# BT8670.net
KiCad netlist of a schematic drawn in Altium Designer
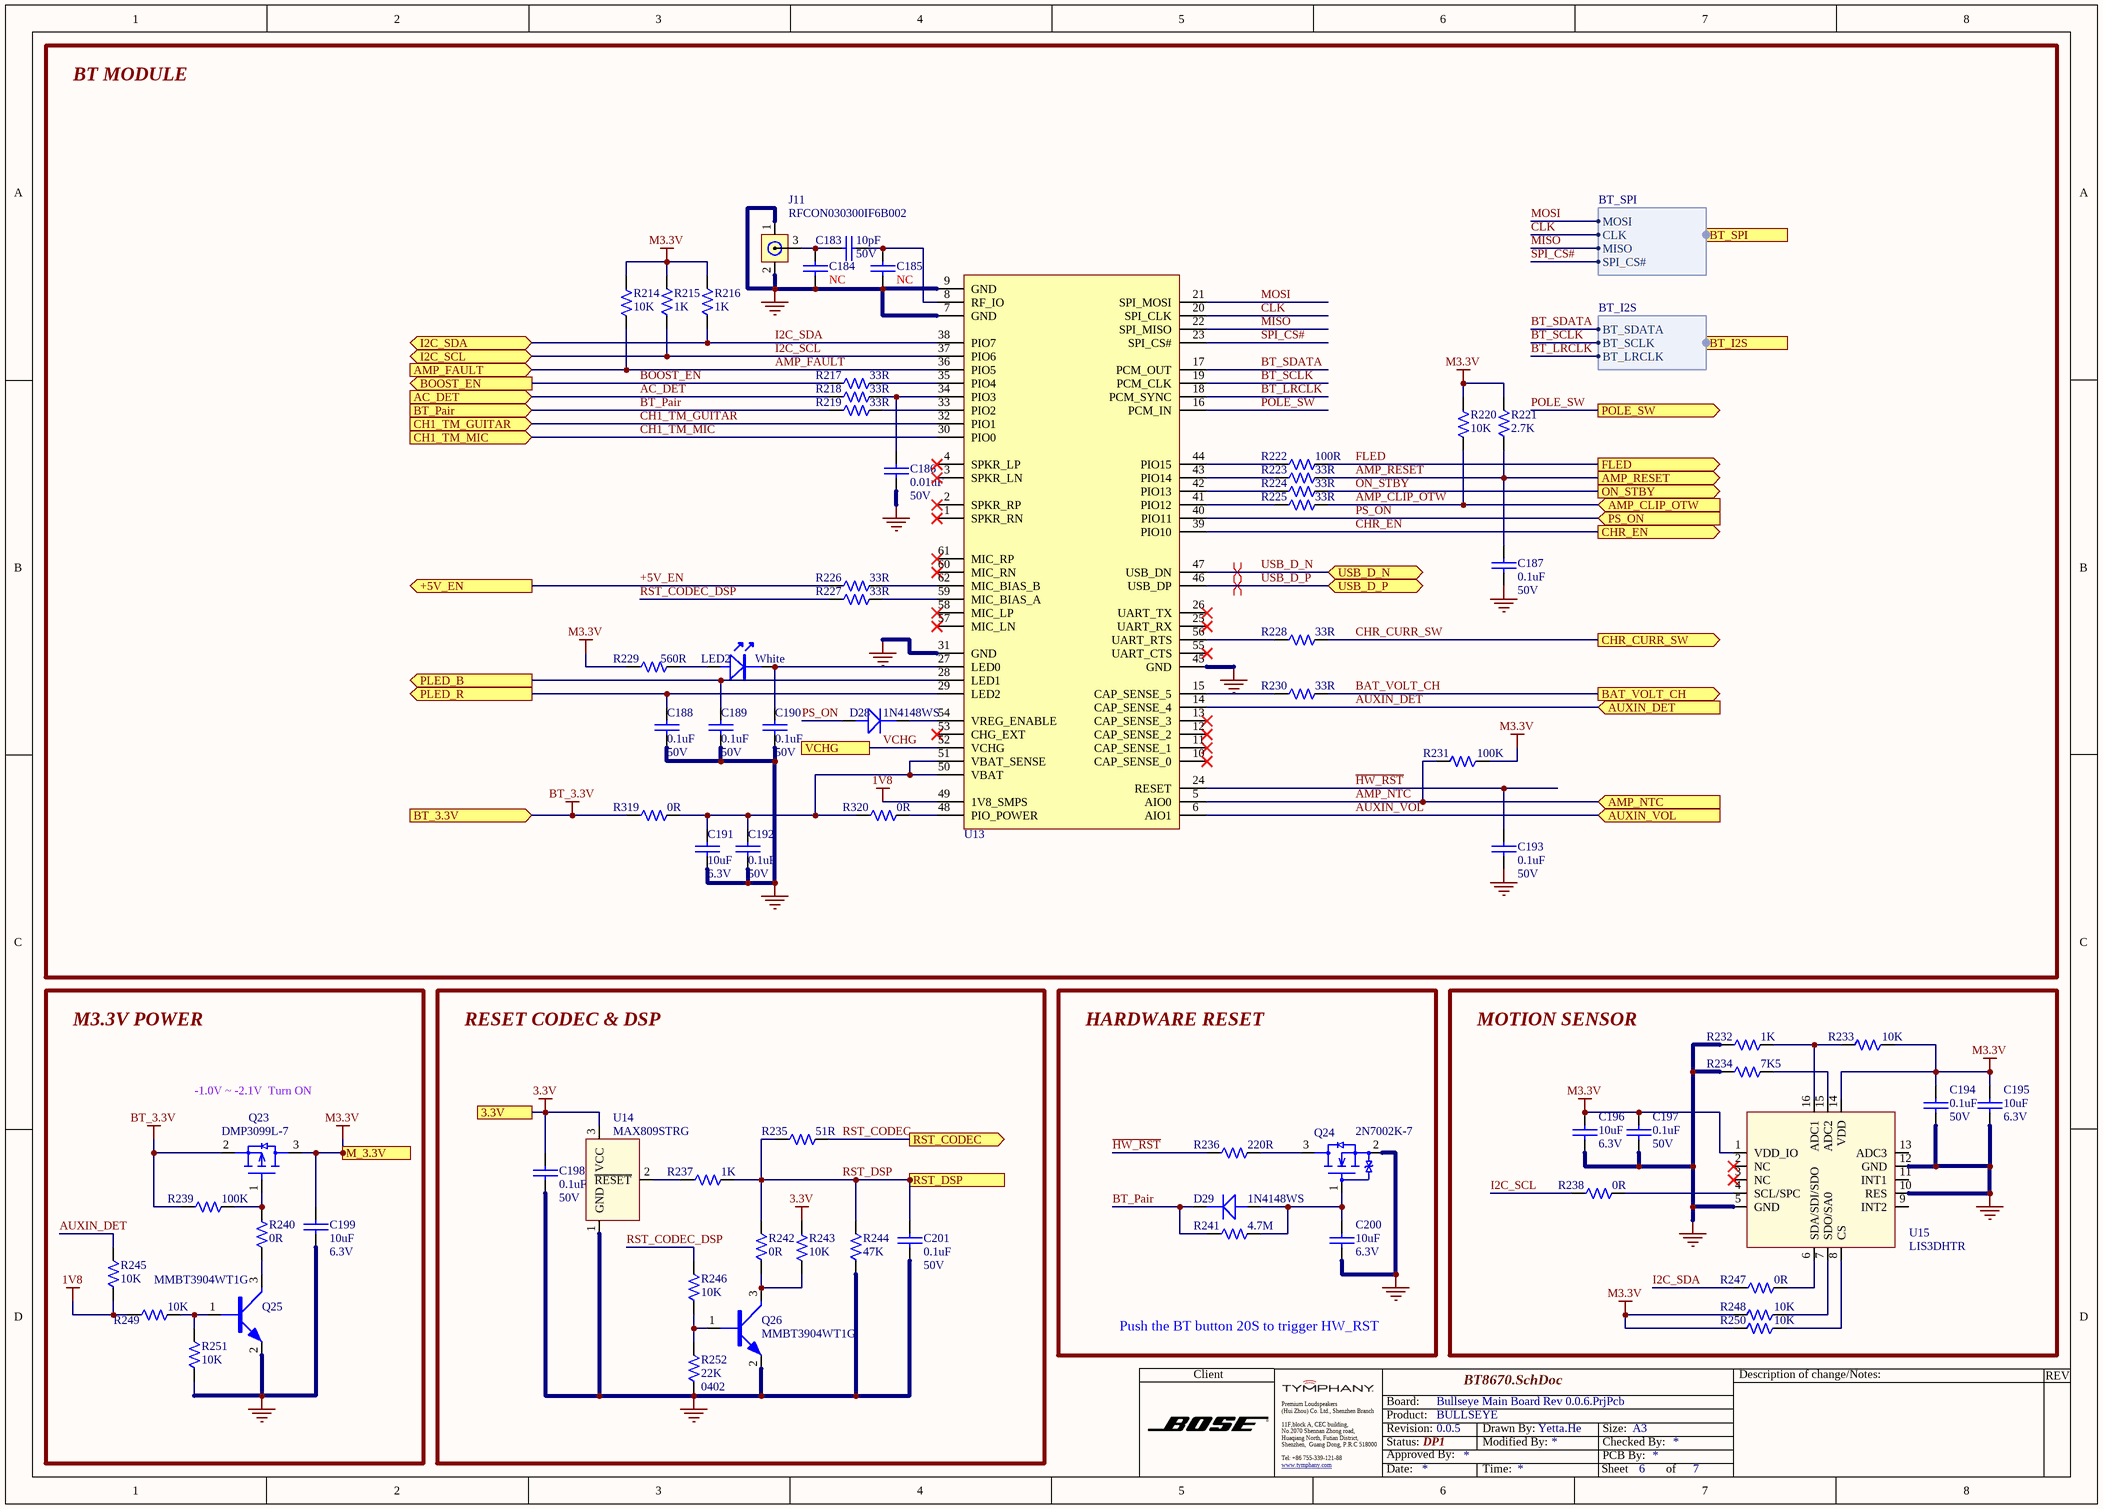
[diagram p0: BT8670.SchDoc]

(export (version "E")
  (design (tool "Eeschema 10.0.6"))
  (components
    (comp (ref "C183")
      (value "10pF")
      (footprint "CAPC0402-RW")
      (description "CHIP CAP 5% 50V 0402 NPO 10pF")
      (fields
        (field (name "TOLERANCE") "5%")
        (field (name "VOLTAGE") "50V")
        (field (name "Comment") "PWL410371-1000")
        (field (name "CREATE_NAME") "TOM@Deftronics")
      )
      (libsource (lib "P-Capacitors") (part "CAP0402 10pF 50V 5%"))
    )
    (comp (ref "C184")
      (value "NC")
      (footprint "CAPC0402-RW")
      (fields (field (name "Comment") "CAP0402 NC") (field (name "CREATE_NAME") "Tom"))
      (libsource (lib "Temporary") (part "CAP0402 NC"))
    )
    (comp (ref "C185")
      (value "NC")
      (footprint "CAPC0402-RW")
      (fields (field (name "Comment") "CAP0402 NC") (field (name "CREATE_NAME") "Tom"))
      (libsource (lib "Temporary") (part "CAP0402 NC"))
    )
    (comp (ref "C186")
      (value "0.01uF")
      (footprint "CAPC0402-RW")
      (description "CAP, CER, 0.01uF, 10%, 50V, X7R, 0402, RoHS")
      (fields
        (field (name "TOLERANCE") "10%")
        (field (name "VOLTAGE") "50V")
        (field (name "Comment") "PWL456470-1030")
        (field (name "CREATE_NAME") "Evan@Deftronics")
      )
      (libsource (lib "P-Capacitors") (part "CAP0402 0.01uF 50V 10%"))
    )
    (comp (ref "C187")
      (value "0.1uF")
      (footprint "CAPC0402-RW")
      (description "CAP X7R .10UF 50V +-10% 0402 WALSIN L")
      (fields
        (field (name "TOLERANCE") "10%")
        (field (name "VOLTAGE") "50V")
        (field (name "Comment") "PWL456470-1040")
        (field (name "CREATE_NAME") "TOM@Deftronics")
      )
      (libsource (lib "P-Capacitors") (part "CAP0402 0.1uF 50V 10%"))
    )
    (comp (ref "C188")
      (value "0.1uF")
      (footprint "CAPC0402-RW")
      (description "CAP X7R .10UF 50V +-10% 0402 WALSIN L")
      (fields
        (field (name "TOLERANCE") "10%")
        (field (name "VOLTAGE") "50V")
        (field (name "Comment") "PWL456470-1040")
        (field (name "CREATE_NAME") "TOM@Deftronics")
      )
      (libsource (lib "P-Capacitors") (part "CAP0402 0.1uF 50V 10%"))
    )
    (comp (ref "C189")
      (value "0.1uF")
      (footprint "CAPC0402-RW")
      (description "CAP X7R .10UF 50V +-10% 0402 WALSIN L")
      (fields
        (field (name "TOLERANCE") "10%")
        (field (name "VOLTAGE") "50V")
        (field (name "Comment") "PWL456470-1040")
        (field (name "CREATE_NAME") "TOM@Deftronics")
      )
      (libsource (lib "P-Capacitors") (part "CAP0402 0.1uF 50V 10%"))
    )
    (comp (ref "C190")
      (value "0.1uF")
      (footprint "CAPC0402-RW")
      (description "CAP X7R .10UF 50V +-10% 0402 WALSIN L")
      (fields
        (field (name "TOLERANCE") "10%")
        (field (name "VOLTAGE") "50V")
        (field (name "Comment") "PWL456470-1040")
        (field (name "CREATE_NAME") "TOM@Deftronics")
      )
      (libsource (lib "P-Capacitors") (part "CAP0402 0.1uF 50V 10%"))
    )
    (comp (ref "C191")
      (value "10uF")
      (footprint "CAPC0603-RW")
      (description "CAP X5R 10UF 6.3V +-10% 0603 SAMSUN L")
      (fields
        (field (name "MFG") "SAMSUNG")
        (field (name "MFG PART") "CL10A106KQ8NNNC")
        (field (name "VOLTAGE") "6.3V")
        (field (name "CREATE_NAME") "Nathan")
      )
      (libsource (lib "P-Capacitors") (part "CAP0603 10uF 6.3V 10%_X5R_SAMSUNG"))
    )
    (comp (ref "C192")
      (value "0.1uF")
      (footprint "CAPC0402-RW")
      (description "CAP X7R .10UF 50V +-10% 0402 WALSIN L")
      (fields
        (field (name "TOLERANCE") "10%")
        (field (name "VOLTAGE") "50V")
        (field (name "Comment") "PWL456470-1040")
        (field (name "CREATE_NAME") "TOM@Deftronics")
      )
      (libsource (lib "P-Capacitors") (part "CAP0402 0.1uF 50V 10%"))
    )
    (comp (ref "C193")
      (value "0.1uF")
      (footprint "CAPC0402-RW")
      (description "CAP X7R .10UF 50V +-10% 0402 WALSIN L")
      (fields
        (field (name "TOLERANCE") "10%")
        (field (name "VOLTAGE") "50V")
        (field (name "Comment") "PWL456470-1040")
        (field (name "CREATE_NAME") "TOM@Deftronics")
      )
      (libsource (lib "P-Capacitors") (part "CAP0402 0.1uF 50V 10%"))
    )
    (comp (ref "C194")
      (value "0.1uF")
      (footprint "CAPC0402-RW")
      (description "CAP X7R .10UF 50V +-10% 0402 WALSIN L")
      (fields
        (field (name "TOLERANCE") "10%")
        (field (name "VOLTAGE") "50V")
        (field (name "Comment") "PWL456470-1040")
        (field (name "CREATE_NAME") "TOM@Deftronics")
      )
      (libsource (lib "P-Capacitors") (part "CAP0402 0.1uF 50V 10%"))
    )
    (comp (ref "C195")
      (value "10uF")
      (footprint "CAPC0603-RW")
      (description "CAP X5R 10UF 6.3V +-10% 0603 SAMSUN L")
      (fields
        (field (name "MFG") "SAMSUNG")
        (field (name "MFG PART") "CL10A106KQ8NNNC")
        (field (name "VOLTAGE") "6.3V")
        (field (name "CREATE_NAME") "Nathan")
      )
      (libsource (lib "P-Capacitors") (part "CAP0603 10uF 6.3V 10%_X5R_SAMSUNG"))
    )
    (comp (ref "C196")
      (value "10uF")
      (footprint "CAPC0603-RW")
      (description "CAP X5R 10UF 6.3V +-10% 0603 SAMSUN L")
      (fields
        (field (name "MFG") "SAMSUNG")
        (field (name "MFG PART") "CL10A106KQ8NNNC")
        (field (name "VOLTAGE") "6.3V")
        (field (name "CREATE_NAME") "Nathan")
      )
      (libsource (lib "P-Capacitors") (part "CAP0603 10uF 6.3V 10%_X5R_SAMSUNG"))
    )
    (comp (ref "C197")
      (value "0.1uF")
      (footprint "CAPC0402-RW")
      (description "CAP X7R .10UF 50V +-10% 0402 WALSIN L")
      (fields
        (field (name "TOLERANCE") "10%")
        (field (name "VOLTAGE") "50V")
        (field (name "Comment") "PWL456470-1040")
        (field (name "CREATE_NAME") "TOM@Deftronics")
      )
      (libsource (lib "P-Capacitors") (part "CAP0402 0.1uF 50V 10%"))
    )
    (comp (ref "C198")
      (value "0.1uF")
      (footprint "CAPC0402-RW")
      (description "CAP X7R .10UF 50V +-10% 0402 WALSIN L")
      (fields
        (field (name "TOLERANCE") "10%")
        (field (name "VOLTAGE") "50V")
        (field (name "Comment") "PWL456470-1040")
        (field (name "CREATE_NAME") "TOM@Deftronics")
      )
      (libsource (lib "P-Capacitors") (part "CAP0402 0.1uF 50V 10%"))
    )
    (comp (ref "C199")
      (value "10uF")
      (footprint "CAPC0603-RW")
      (description "CAP X5R 10UF 6.3V +-10% 0603 SAMSUN L")
      (fields
        (field (name "MFG") "SAMSUNG")
        (field (name "MFG PART") "CL10A106KQ8NNNC")
        (field (name "VOLTAGE") "6.3V")
        (field (name "CREATE_NAME") "Nathan")
      )
      (libsource (lib "P-Capacitors") (part "CAP0603 10uF 6.3V 10%_X5R_SAMSUNG"))
    )
    (comp (ref "C200")
      (value "10uF")
      (footprint "CAPC0603-RW")
      (description "CAP X5R 10UF 6.3V +-10% 0603 SAMSUN L")
      (fields
        (field (name "MFG") "SAMSUNG")
        (field (name "MFG PART") "CL10A106KQ8NNNC")
        (field (name "VOLTAGE") "6.3V")
        (field (name "CREATE_NAME") "Nathan")
      )
      (libsource (lib "P-Capacitors") (part "CAP0603 10uF 6.3V 10%_X5R_SAMSUNG"))
    )
    (comp (ref "C201")
      (value "0.1uF")
      (footprint "CAPC0402-RW")
      (description "CAP X7R .10UF 50V +-10% 0402 WALSIN L")
      (fields
        (field (name "TOLERANCE") "10%")
        (field (name "VOLTAGE") "50V")
        (field (name "Comment") "PWL456470-1040")
        (field (name "CREATE_NAME") "TOM@Deftronics")
      )
      (libsource (lib "P-Capacitors") (part "CAP0402 0.1uF 50V 10%"))
    )
    (comp (ref "D28")
      (value "RCD114148-0020")
      (footprint "SOD-323")
      (description "DIODE SW 1N4148 VF=0.7V SOD-323")
      (fields
        (field (name "MFG") "TW SEMICONDUCTOR")
        (field (name "VOLTAGE") "100V")
        (field (name "MFG PART") "1N4148WS")
      )
      (libsource (lib "R-Semiconductors") (part "1N4148WS"))
    )
    (comp (ref "D29")
      (value "RCD114148-0020")
      (footprint "SOD-323")
      (description "DIODE SW 1N4148 VF=0.7V SOD-323")
      (fields
        (field (name "MFG") "TW SEMICONDUCTOR")
        (field (name "VOLTAGE") "100V")
        (field (name "MFG PART") "1N4148WS")
      )
      (libsource (lib "R-Semiconductors") (part "1N4148WS"))
    )
    (comp (ref "J11")
      (value "T690300090900")
      (footprint "RF IPEXSOCKET RFCON030300IF6B00")
      (description "CONN RF IPEXSOCKET WALSIN 3.1*3.0*1.25 K")
      (fields
        (field (name "MFG") "WALSIN")
        (field (name "MFG PART") "RFCON030300IF6B002")
        (field (name "CREATE_NAME") "Nathan")
      )
      (libsource (lib "C-Connector") (part "RF IPEXSOCKET RFCON030300IF6B00"))
    )
    (comp (ref "LED2")
      (value "T575006150202")
      (footprint "LED0603_WHITE")
      (description "LED WHI 0603 19-217-T1D-A EVERLIGH K")
      (fields
        (field (name "MFG PART") "19-217-T1D-AQRHY-3T")
        (field (name "MFG") "EVERLIGHT(億光)")
        (field (name "COLOR") "White")
        (field (name "CREAT NAME") "Nathan")
      )
      (libsource (lib "K-LED-FUSE") (part "LED0603W_19-217-T1D-AQRHY-3T"))
    )
    (comp (ref "Q23")
      (value "T585002550438")
      (footprint "SOT23-132-RW")
      (description "PMOS 20V DMP3099L-7 SOT23 DIODES K")
      (fields
        (field (name "MFG") "DIODES  (ZETEX)")
        (field (name "MFG PART") "DMP3099L-7")
        (field (name "CREATE_NAME") "Nathan")
      )
      (libsource (lib "R-Semiconductors") (part "DMP3099L-7"))
    )
    (comp (ref "Q24")
      (value "T586003230438")
      (footprint "SOT23-132-RW")
      (description "NMOS 60V 2N7002K-7 SOT23 DIODES K")
      (fields
        (field (name "VOLTAGE") "60V")
        (field (name "MFG") "DIODES  (ZETEX)")
        (field (name "MFG PART") "2N7002K-7")
        (field (name "CREATE_NAME") "Nathan")
      )
      (libsource (lib "R-Semiconductors") (part "2N7002K-7"))
    )
    (comp (ref "Q25")
      (value "T581004222440")
      (footprint "SOT323(SC-70)-R")
      (description "NPN 40V MMBT3904WT1G SC70 ( ON K")
      (fields
        (field (name "MFG") "ON")
        (field (name "MFG PART") "MMBT3904WT1G")
        (field (name "CREATE_NAME") "Nathan")
      )
      (libsource (lib "R-Semiconductors") (part "MMBT3904WT1G"))
    )
    (comp (ref "Q26")
      (value "T581004222440")
      (footprint "SOT323(SC-70)-R")
      (description "NPN 40V MMBT3904WT1G SC70 ( ON K")
      (fields
        (field (name "MFG") "ON")
        (field (name "MFG PART") "MMBT3904WT1G")
        (field (name "CREATE_NAME") "Nathan")
      )
      (libsource (lib "R-Semiconductors") (part "MMBT3904WT1G"))
    )
    (comp (ref "R214")
      (value "10K")
      (footprint "0402-RW")
      (description "CHIP RES 10K OHM 1/16W 1% 0402")
      (fields (field (name "POWER") "1/16W") (field (name "MFG") "WALSIN"))
      (libsource (lib "Q-Resistors") (part "RES0402 1/16W 1% 10K OHM"))
    )
    (comp (ref "R215")
      (value "1K")
      (footprint "0402-RW")
      (description "CHIP RES 1K OHM 1/16W 1% 0402")
      (fields (field (name "POWER") "1/16W") (field (name "MFG") "WALSIN"))
      (libsource (lib "Q-Resistors") (part "RES0402 1/16W 1% 1K OHM"))
    )
    (comp (ref "R216")
      (value "1K")
      (footprint "0402-RW")
      (description "CHIP RES 1K OHM 1/16W 1% 0402")
      (fields (field (name "POWER") "1/16W") (field (name "MFG") "WALSIN"))
      (libsource (lib "Q-Resistors") (part "RES0402 1/16W 1% 1K OHM"))
    )
    (comp (ref "R217")
      (value "33R")
      (footprint "0402-RW")
      (description "CHIP RES 33 OHM 1/16W 1% 0402")
      (fields (field (name "POWER") "1/16W") (field (name "MFG") "WALSIN"))
      (libsource (lib "Q-Resistors") (part "RES0402 1/16W 1% 33 OHM"))
    )
    (comp (ref "R218")
      (value "33R")
      (footprint "0402-RW")
      (description "CHIP RES 33 OHM 1/16W 1% 0402")
      (fields (field (name "POWER") "1/16W") (field (name "MFG") "WALSIN"))
      (libsource (lib "Q-Resistors") (part "RES0402 1/16W 1% 33 OHM"))
    )
    (comp (ref "R219")
      (value "33R")
      (footprint "0402-RW")
      (description "CHIP RES 33 OHM 1/16W 1% 0402")
      (fields (field (name "POWER") "1/16W") (field (name "MFG") "WALSIN"))
      (libsource (lib "Q-Resistors") (part "RES0402 1/16W 1% 33 OHM"))
    )
    (comp (ref "R220")
      (value "10K")
      (footprint "0402-RW")
      (description "CHIP RES 10K OHM 1/16W 1% 0402")
      (fields (field (name "POWER") "1/16W") (field (name "MFG") "WALSIN"))
      (libsource (lib "Q-Resistors") (part "RES0402 1/16W 1% 10K OHM"))
    )
    (comp (ref "R221")
      (value "2.7K")
      (footprint "0402-RW")
      (description "CHIP RES 2.7K OHM 1/16W 1% 0402")
      (fields (field (name "POWER") "1/16W") (field (name "MFG") "WALSIN"))
      (libsource (lib "Q-Resistors") (part "RES0402 1/16W 1% 2.7K OHM"))
    )
    (comp (ref "R222")
      (value "100R")
      (footprint "0603-RW")
      (description "CHIP 100 OHM 100PPM +-1% 0603 WALS L")
      (fields (field (name "POWER") "1/10W") (field (name "MFG") "WALSIN (華新)"))
      (libsource (lib "Q-Resistors") (part "RES0603 1/10W 1% 100 OHM"))
    )
    (comp (ref "R223")
      (value "33R")
      (footprint "0402-RW")
      (description "CHIP RES 33 OHM 1/16W 1% 0402")
      (fields (field (name "POWER") "1/16W") (field (name "MFG") "WALSIN"))
      (libsource (lib "Q-Resistors") (part "RES0402 1/16W 1% 33 OHM"))
    )
    (comp (ref "R224")
      (value "33R")
      (footprint "0402-RW")
      (description "CHIP RES 33 OHM 1/16W 1% 0402")
      (fields (field (name "POWER") "1/16W") (field (name "MFG") "WALSIN"))
      (libsource (lib "Q-Resistors") (part "RES0402 1/16W 1% 33 OHM"))
    )
    (comp (ref "R225")
      (value "33R")
      (footprint "0402-RW")
      (description "CHIP RES 33 OHM 1/16W 1% 0402")
      (fields (field (name "POWER") "1/16W") (field (name "MFG") "WALSIN"))
      (libsource (lib "Q-Resistors") (part "RES0402 1/16W 1% 33 OHM"))
    )
    (comp (ref "R226")
      (value "33R")
      (footprint "0402-RW")
      (description "CHIP RES 33 OHM 1/16W 1% 0402")
      (fields (field (name "POWER") "1/16W") (field (name "MFG") "WALSIN"))
      (libsource (lib "Q-Resistors") (part "RES0402 1/16W 1% 33 OHM"))
    )
    (comp (ref "R227")
      (value "33R")
      (footprint "0402-RW")
      (description "CHIP RES 33 OHM 1/16W 1% 0402")
      (fields (field (name "POWER") "1/16W") (field (name "MFG") "WALSIN"))
      (libsource (lib "Q-Resistors") (part "RES0402 1/16W 1% 33 OHM"))
    )
    (comp (ref "R228")
      (value "33R")
      (footprint "0402-RW")
      (description "CHIP RES 33 OHM 1/16W 1% 0402")
      (fields (field (name "POWER") "1/16W") (field (name "MFG") "WALSIN"))
      (libsource (lib "Q-Resistors") (part "RES0402 1/16W 1% 33 OHM"))
    )
    (comp (ref "R229")
      (value "560R")
      (footprint "0603-RW")
      (description "GP CHIP RES. 560 OHM 1/10W 1% 0603")
      (fields (field (name "Comment") "QCF011030-5600"))
      (libsource (lib "Q-Resistors") (part "RES0603 1/10W 1% 560 OHM"))
    )
    (comp (ref "R230")
      (value "33R")
      (footprint "0402-RW")
      (description "CHIP RES 33 OHM 1/16W 1% 0402")
      (fields (field (name "POWER") "1/16W") (field (name "MFG") "WALSIN"))
      (libsource (lib "Q-Resistors") (part "RES0402 1/16W 1% 33 OHM"))
    )
    (comp (ref "R231")
      (value "100K")
      (footprint "0603-RW")
      (description "GP CHIP RES. 100K OHM 1/10W 1% 0603")
      (fields (field (name "POWER") "1/10W") (field (name "Comment") "QCF011030-1003"))
      (libsource (lib "Q-Resistors") (part "RES0603 1/10W 1% 100K OHM"))
    )
    (comp (ref "R232")
      (value "1K")
      (footprint "0402-RW")
      (description "CHIP RES 1K OHM 1/16W 1% 0402")
      (fields (field (name "POWER") "1/16W") (field (name "MFG") "WALSIN"))
      (libsource (lib "Q-Resistors") (part "RES0402 1/16W 1% 1K OHM"))
    )
    (comp (ref "R233")
      (value "10K")
      (footprint "0402-RW")
      (description "CHIP RES 10K OHM 1/16W 1% 0402")
      (fields (field (name "POWER") "1/16W") (field (name "MFG") "WALSIN"))
      (libsource (lib "Q-Resistors") (part "RES0402 1/16W 1% 10K OHM"))
    )
    (comp (ref "R234")
      (value "7K5")
      (footprint "0603-RW")
      (description "CHIP RES 7.5K OHM 1/10W 1% 0603")
      (fields
        (field (name "POWER") "1/10W")
        (field (name "Comment") "QCF011030-7501")
        (field (name "CREATE_NAME") "Nathan")
      )
      (libsource (lib "Q-Resistors") (part "RES0603 1/10W 1% 7.5K OHM"))
    )
    (comp (ref "R235")
      (value "51R")
      (footprint "0402-RW")
      (description "CHIP RES  51 OHM 1/16W 1% 0402")
      (fields
        (field (name "POWER") "1/16W")
        (field (name "Comment") "QCF161240-5109")
        (field (name "CREATE_NAME") "GordonL@Deftronics")
      )
      (libsource (lib "Q-Resistors") (part "RES0402 1/16W 1% 51 OHM"))
    )
    (comp (ref "R236")
      (value "220R")
      (footprint "0402-RW")
      (description "CHIP RES 220 OHM 1/16W 1% 0402")
      (fields (field (name "MFG") "WALSIN") (field (name "Comment") "QCF161240-2200"))
      (libsource (lib "Q-Resistors") (part "RES0402 1/16W 1% 220 OHM"))
    )
    (comp (ref "R237")
      (value "1K")
      (footprint "0603-RW")
      (description "GP CHIP RES. 1K OHM 1/10W 1% 0603")
      (fields (field (name "Comment") "QCF011030-1001"))
      (libsource (lib "Q-Resistors") (part "RES0603 1/10W 1% 1K OHM"))
    )
    (comp (ref "R238")
      (value "0R")
      (footprint "0603-RW")
      (description "CHIP 0 OHM 0 OHM 0 OHM 0603 WALSIN L")
      (fields (field (name "POWER") "1/10W") (field (name "MFG PART") "WR06X000PTL"))
      (libsource (lib "Q-Resistors") (part "RES0603 1/10W 0 OHM_WALSIN"))
    )
    (comp (ref "R239")
      (value "100K")
      (footprint "0603-RW")
      (description "GP CHIP RES. 100K OHM 1/10W 1% 0603")
      (fields (field (name "POWER") "1/10W") (field (name "Comment") "QCF011030-1003"))
      (libsource (lib "Q-Resistors") (part "RES0603 1/10W 1% 100K OHM"))
    )
    (comp (ref "R240")
      (value "0R")
      (footprint "0603-RW")
      (description "CHIP 0 OHM 0 OHM 0 OHM 0603 WALSIN L")
      (fields (field (name "POWER") "1/10W") (field (name "MFG PART") "WR06X000PTL"))
      (libsource (lib "Q-Resistors") (part "RES0603 1/10W 0 OHM_WALSIN"))
    )
    (comp (ref "R241")
      (value "4.7M")
      (footprint "0603-RW")
      (description "CHIP RES 4.7M OHM 1/10W 1% 0603")
      (fields (field (name "Comment") "QCF011030-4704"))
      (libsource (lib "Q-Resistors") (part "RES0603 1/10W 1% 4.7M OHM"))
    )
    (comp (ref "R242")
      (value "0R")
      (footprint "0603-RW")
      (description "CHIP 0 OHM 0 OHM 0 OHM 0603 WALSIN L")
      (fields (field (name "MFG PART") "WR06X000PTL") (field (name "MFG") "WALSIN (華新)"))
      (libsource (lib "Q-Resistors") (part "RES0603 1/10W 0 OHM_WALSIN"))
    )
    (comp (ref "R243")
      (value "10K")
      (footprint "0402-RW")
      (description "CHIP RES 10K OHM 1/16W 1% 0402")
      (fields (field (name "POWER") "1/16W") (field (name "MFG") "WALSIN"))
      (libsource (lib "Q-Resistors") (part "RES0402 1/16W 1% 10K OHM"))
    )
    (comp (ref "R244")
      (value "47K")
      (footprint "0603-RW")
      (description "GP CHIP RES. 47K OHM 1/10W 1% 0603")
      (fields (field (name "POWER") "1/10W") (field (name "Comment") "QCF011030-4702"))
      (libsource (lib "Q-Resistors") (part "RES0603 1/10W 1% 47K OHM"))
    )
    (comp (ref "R245")
      (value "10K")
      (footprint "0402-RW")
      (description "CHIP RES 10K OHM 1/16W 1% 0402")
      (fields (field (name "POWER") "1/16W") (field (name "MFG") "WALSIN"))
      (libsource (lib "Q-Resistors") (part "RES0402 1/16W 1% 10K OHM"))
    )
    (comp (ref "R246")
      (value "10K")
      (footprint "0402-RW")
      (description "CHIP RES 10K OHM 1/16W 1% 0402")
      (fields (field (name "POWER") "1/16W") (field (name "MFG") "WALSIN"))
      (libsource (lib "Q-Resistors") (part "RES0402 1/16W 1% 10K OHM"))
    )
    (comp (ref "R247")
      (value "0R")
      (footprint "0603-RW")
      (description "CHIP 0 OHM 0 OHM 0 OHM 0603 WALSIN L")
      (fields (field (name "POWER") "1/10W") (field (name "MFG PART") "WR06X000PTL"))
      (libsource (lib "Q-Resistors") (part "RES0603 1/10W 0 OHM_WALSIN"))
    )
    (comp (ref "R248")
      (value "10K")
      (footprint "0402-RW")
      (description "CHIP RES 10K OHM 1/16W 1% 0402")
      (fields (field (name "POWER") "1/16W") (field (name "MFG") "WALSIN"))
      (libsource (lib "Q-Resistors") (part "RES0402 1/16W 1% 10K OHM"))
    )
    (comp (ref "R249")
      (value "10K")
      (footprint "0402-RW")
      (description "CHIP RES 10K OHM 1/16W 1% 0402")
      (fields (field (name "POWER") "1/16W") (field (name "MFG") "WALSIN"))
      (libsource (lib "Q-Resistors") (part "RES0402 1/16W 1% 10K OHM"))
    )
    (comp (ref "R250")
      (value "10K")
      (footprint "0402-RW")
      (description "CHIP RES 10K OHM 1/16W 1% 0402")
      (fields (field (name "POWER") "1/16W") (field (name "MFG") "WALSIN"))
      (libsource (lib "Q-Resistors") (part "RES0402 1/16W 1% 10K OHM"))
    )
    (comp (ref "R251")
      (value "10K")
      (footprint "0402-RW")
      (description "CHIP RES 10K OHM 1/16W 1% 0402")
      (fields (field (name "POWER") "1/16W") (field (name "MFG") "WALSIN"))
      (libsource (lib "Q-Resistors") (part "RES0402 1/16W 1% 10K OHM"))
    )
    (comp (ref "R252")
      (value "22K")
      (footprint "0402-RW")
      (description "CHIP RES 22K OHM 1/16W 1% 0402")
      (fields
        (field (name "MFG") "WALSIN")
        (field (name "PACKAGE") "0402")
        (field (name "Comment") "QCF161240-2202")
      )
      (libsource (lib "Q-Resistors") (part "RES0402 1/16W 1% 22K OHM"))
    )
    (comp (ref "R319")
      (value "0R")
      (footprint "0603-RW")
      (description "CHIP 0 OHM 0 OHM 0 OHM 0603 WALSIN L")
      (fields (field (name "POWER") "1/10W") (field (name "MFG PART") "WR06X000PTL"))
      (libsource (lib "Q-Resistors") (part "RES0603 1/10W 0 OHM_WALSIN"))
    )
    (comp (ref "R320")
      (value "0R")
      (footprint "0603-RW")
      (description "CHIP 0 OHM 0 OHM 0 OHM 0603 WALSIN L")
      (fields (field (name "POWER") "1/10W") (field (name "MFG PART") "WR06X000PTL"))
      (libsource (lib "Q-Resistors") (part "RES0603 1/10W 0 OHM_WALSIN"))
    )
    (comp (ref "U13")
      (value "WPCA00101-X001/0001")
      (footprint "BTM-865")
      (description "BOSE CHIBI BT F/W V1.0 CHIBI K")
      (fields
        (field (name "MFG PART") "BTM865")
        (field (name "MFG") "RAYSON")
        (field (name "CREATE_NAME") "Nathan")
      )
      (libsource (lib "W-SUBASS-Parts") (part "BTM865_BOSE CHIBI"))
    )
    (comp (ref "U14")
      (value "T610300090588")
      (footprint "SOT23-132-SW")
      (description "MCU MAX809STRG SOT23-3 ON SEMI G")
      (fields (field (name "MFG") "ON SEMI") (field (name "MFG PART") "MAX809STRG"))
      (libsource (lib "R-Semiconductors") (part "MAX809STRG_ON SEMI"))
    )
    (comp (ref "U15")
      (value "T611100028639")
      (footprint "LGA-16")
      (description "A\\D LIS3DHTR LGA-16 ST K")
      (fields
        (field (name "MFG") "ST")
        (field (name "MFG PART") "LIS3DHTR")
        (field (name "CREATE_NAME") "Nathan")
      )
      (libsource (lib "R-Semiconductors") (part "LIS3DHTR"))
    )
  )
  (nets
    (net (code "3") (name "/+5V_EN") (class "Default")
      (node (ref "R226") (pin "1") (pinfunction "1_1") (pintype "passive"))
    )
    (net (code "4") (name "/AC_DET") (class "Default")
      (node (ref "R218") (pin "1") (pinfunction "1_1") (pintype "passive"))
    )
    (net (code "5") (name "/AMP_CLIP_OTW") (class "Default")
      (node (ref "R220") (pin "2") (pinfunction "2_2") (pintype "passive"))
      (node (ref "R225") (pin "2") (pinfunction "2_2") (pintype "passive"))
    )
    (net (code "6") (name "/AMP_FAULT") (class "Default")
      (node (ref "R214") (pin "2") (pinfunction "2_2") (pintype "passive"))
      (node (ref "U13") (pin "36") (pinfunction "PIO5_36") (pintype "passive"))
    )
    (net (code "7") (name "/AMP_NTC") (class "Default")
      (node (ref "R231") (pin "2") (pinfunction "2_2") (pintype "passive"))
      (node (ref "U13") (pin "5") (pinfunction "AIO0_5") (pintype "passive"))
    )
    (net (code "8") (name "/AMP_RESET") (class "Default")
      (node (ref "C187") (pin "1") (pinfunction "1_1") (pintype "passive"))
      (node (ref "R221") (pin "1") (pinfunction "1_1") (pintype "passive"))
      (node (ref "R223") (pin "2") (pinfunction "2_2") (pintype "passive"))
    )
    (net (code "9") (name "/AUXIN_DET") (class "Default")
      (node (ref "R245") (pin "2") (pinfunction "2_2") (pintype "passive"))
      (node (ref "U13") (pin "14") (pinfunction "CAP_SENSE_4_14") (pintype "passive"))
    )
    (net (code "10") (name "/AUXIN_VOL") (class "Default")
      (node (ref "U13") (pin "6") (pinfunction "AIO1_6") (pintype "passive"))
    )
    (net (code "11") (name "/BAT_VOLT_CH") (class "Default")
      (node (ref "R230") (pin "2") (pinfunction "2_2") (pintype "passive"))
    )
    (net (code "12") (name "/BOOST_EN") (class "Default")
      (node (ref "R217") (pin "1") (pinfunction "1_1") (pintype "passive"))
    )
    (net (code "13") (name "/BT_LRCLK") (class "Default")
      (node (ref "U13") (pin "18") (pinfunction "PCM_SYNC_18") (pintype "passive"))
    )
    (net (code "14") (name "/BT_Pair") (class "Default")
      (node (ref "D29") (pin "2") (pinfunction "K_2") (pintype "passive"))
      (node (ref "R219") (pin "1") (pinfunction "1_1") (pintype "passive"))
      (node (ref "R241") (pin "1") (pinfunction "1_1") (pintype "passive"))
    )
    (net (code "15") (name "/BT_SCLK") (class "Default")
      (node (ref "U13") (pin "19") (pinfunction "PCM_CLK_19") (pintype "passive"))
    )
    (net (code "16") (name "/BT_SDATA") (class "Default")
      (node (ref "U13") (pin "17") (pinfunction "PCM_OUT_17") (pintype "passive"))
    )
    (net (code "17") (name "/CH1_TM_GUITAR") (class "Default")
      (node (ref "U13") (pin "32") (pinfunction "PIO1_32") (pintype "passive"))
    )
    (net (code "18") (name "/CH1_TM_MIC") (class "Default")
      (node (ref "U13") (pin "30") (pinfunction "PIO0_30") (pintype "passive"))
    )
    (net (code "19") (name "/CHR_CURR_SW") (class "Default")
      (node (ref "R228") (pin "2") (pinfunction "2_2") (pintype "passive"))
    )
    (net (code "20") (name "/CHR_EN") (class "Default")
      (node (ref "U13") (pin "39") (pinfunction "PIO10_39") (pintype "passive"))
    )
    (net (code "21") (name "/CLK") (class "Default")
      (node (ref "U13") (pin "20") (pinfunction "SPI_CLK_20") (pintype "passive"))
    )
    (net (code "22") (name "/FLED") (class "Default")
      (node (ref "R222") (pin "2") (pinfunction "2_2") (pintype "passive"))
    )
    (net (code "23") (name "/I2C_SCL") (class "Default")
      (node (ref "R215") (pin "1") (pinfunction "1_1") (pintype "passive"))
      (node (ref "R238") (pin "1") (pinfunction "1_1") (pintype "passive"))
      (node (ref "U13") (pin "37") (pinfunction "PIO6_37") (pintype "passive"))
    )
    (net (code "24") (name "/I2C_SDA") (class "Default")
      (node (ref "R216") (pin "1") (pinfunction "1_1") (pintype "passive"))
      (node (ref "R247") (pin "1") (pinfunction "1_1") (pintype "passive"))
      (node (ref "U13") (pin "38") (pinfunction "PIO7_38") (pintype "passive"))
    )
    (net (code "25") (name "/MISO") (class "Default")
      (node (ref "U13") (pin "22") (pinfunction "SPI_MISO_22") (pintype "passive"))
    )
    (net (code "26") (name "/MOSI") (class "Default")
      (node (ref "U13") (pin "21") (pinfunction "SPI_MOSI_21") (pintype "passive"))
    )
    (net (code "27") (name "/ON_STBY") (class "Default")
      (node (ref "R224") (pin "2") (pinfunction "2_2") (pintype "passive"))
    )
    (net (code "28") (name "/PLED_B") (class "Default")
      (node (ref "C189") (pin "1") (pinfunction "1_1") (pintype "passive"))
      (node (ref "U13") (pin "28") (pinfunction "LED1_28") (pintype "passive"))
    )
    (net (code "29") (name "/PLED_R") (class "Default")
      (node (ref "C188") (pin "1") (pinfunction "1_1") (pintype "passive"))
      (node (ref "U13") (pin "29") (pinfunction "LED2_29") (pintype "passive"))
    )
    (net (code "30") (name "/POLE_SW") (class "Default")
      (node (ref "U13") (pin "16") (pinfunction "PCM_IN_16") (pintype "passive"))
    )
    (net (code "31") (name "/PS_ON") (class "Default")
      (node (ref "D28") (pin "1") (pinfunction "A_1") (pintype "passive"))
      (node (ref "U13") (pin "40") (pinfunction "PIO11_40") (pintype "passive"))
    )
    (net (code "32") (name "/RST_CODEC") (class "Default")
      (node (ref "R235") (pin "2") (pinfunction "2_2") (pintype "passive"))
    )
    (net (code "33") (name "/RST_CODEC_DSP") (class "Default")
      (node (ref "R227") (pin "1") (pinfunction "1_1") (pintype "passive"))
      (node (ref "R246") (pin "2") (pinfunction "2_2") (pintype "passive"))
    )
    (net (code "34") (name "/RST_DSP") (class "Default")
      (node (ref "C201") (pin "1") (pinfunction "1_1") (pintype "passive"))
      (node (ref "R235") (pin "1") (pinfunction "1_1") (pintype "passive"))
      (node (ref "R237") (pin "2") (pinfunction "2_2") (pintype "passive"))
      (node (ref "R242") (pin "2") (pinfunction "2_2") (pintype "passive"))
      (node (ref "R244") (pin "2") (pinfunction "2_2") (pintype "passive"))
    )
    (net (code "35") (name "/SPI_CS#") (class "Default")
      (node (ref "U13") (pin "23") (pinfunction "SPI_CS#_23") (pintype "passive"))
    )
    (net (code "36") (name "/USB_D_N") (class "Default")
      (node (ref "U13") (pin "47") (pinfunction "USB_DN_47") (pintype "passive"))
    )
    (net (code "37") (name "/USB_D_P") (class "Default")
      (node (ref "U13") (pin "46") (pinfunction "USB_DP_46") (pintype "passive"))
    )
    (net (code "38") (name "/VCHG") (class "Default")
      (node (ref "U13") (pin "52") (pinfunction "VCHG_52") (pintype "passive"))
    )
    (net (code "41") (name "/~{HW_RST}") (class "Default")
      (node (ref "C193") (pin "1") (pinfunction "1_1") (pintype "passive"))
      (node (ref "R236") (pin "1") (pinfunction "1_1") (pintype "passive"))
      (node (ref "U13") (pin "24") (pinfunction "RESET_24") (pintype "passive"))
    )
    (net (code "42") (name "1V8") (class "Default")
      (node (ref "R245") (pin "1") (pinfunction "1_1") (pintype "passive"))
      (node (ref "R249") (pin "1") (pinfunction "1_1") (pintype "passive"))
      (node (ref "U13") (pin "49") (pinfunction "1V8_SMPS_49") (pintype "passive"))
    )
    (net (code "43") (name "3.3V") (class "Default")
      (node (ref "C198") (pin "1") (pinfunction "1_1") (pintype "passive"))
      (node (ref "R243") (pin "1") (pinfunction "1_1") (pintype "passive"))
      (node (ref "U14") (pin "3") (pinfunction "VCC_3") (pintype "passive"))
    )
    (net (code "44") (name "BT_3.3V") (class "Default")
      (node (ref "Q23") (pin "2") (pinfunction "S_2") (pintype "passive"))
      (node (ref "R239") (pin "1") (pinfunction "1_1") (pintype "passive"))
      (node (ref "R319") (pin "1") (pinfunction "1_1") (pintype "passive"))
    )
    (net (code "45") (name "GND") (class "Default")
      (node (ref "C184") (pin "2") (pinfunction "2_2") (pintype "passive"))
      (node (ref "C185") (pin "2") (pinfunction "2_2") (pintype "passive"))
      (node (ref "C186") (pin "1") (pinfunction "1_1") (pintype "passive"))
      (node (ref "C187") (pin "2") (pinfunction "2_2") (pintype "passive"))
      (node (ref "C188") (pin "2") (pinfunction "2_2") (pintype "passive"))
      (node (ref "C189") (pin "2") (pinfunction "2_2") (pintype "passive"))
      (node (ref "C190") (pin "2") (pinfunction "2_2") (pintype "passive"))
      (node (ref "C191") (pin "2") (pinfunction "2_2") (pintype "passive"))
      (node (ref "C192") (pin "2") (pinfunction "2_2") (pintype "passive"))
      (node (ref "C193") (pin "2") (pinfunction "2_2") (pintype "passive"))
      (node (ref "C194") (pin "2") (pinfunction "2_2") (pintype "passive"))
      (node (ref "C195") (pin "2") (pinfunction "2_2") (pintype "passive"))
      (node (ref "C196") (pin "2") (pinfunction "2_2") (pintype "passive"))
      (node (ref "C197") (pin "2") (pinfunction "2_2") (pintype "passive"))
      (node (ref "C198") (pin "2") (pinfunction "2_2") (pintype "passive"))
      (node (ref "C199") (pin "2") (pinfunction "2_2") (pintype "passive"))
      (node (ref "C200") (pin "2") (pinfunction "2_2") (pintype "passive"))
      (node (ref "C201") (pin "2") (pinfunction "2_2") (pintype "passive"))
      (node (ref "J11") (pin "1") (pinfunction "GND_1") (pintype "passive"))
      (node (ref "J11") (pin "2") (pinfunction "GND_2") (pintype "passive"))
      (node (ref "Q24") (pin "2") (pinfunction "S_2") (pintype "passive"))
      (node (ref "Q25") (pin "2") (pinfunction "E_2") (pintype "passive"))
      (node (ref "Q26") (pin "2") (pinfunction "E_2") (pintype "passive"))
      (node (ref "R232") (pin "1") (pinfunction "1_1") (pintype "passive"))
      (node (ref "R234") (pin "1") (pinfunction "1_1") (pintype "passive"))
      (node (ref "R244") (pin "1") (pinfunction "1_1") (pintype "passive"))
      (node (ref "R251") (pin "1") (pinfunction "1_1") (pintype "passive"))
      (node (ref "R252") (pin "1") (pinfunction "1_1") (pintype "passive"))
      (node (ref "U13") (pin "31") (pinfunction "GND_31") (pintype "passive"))
      (node (ref "U13") (pin "45") (pinfunction "GND_45") (pintype "passive"))
      (node (ref "U13") (pin "7") (pinfunction "GND_7") (pintype "passive"))
      (node (ref "U13") (pin "9") (pinfunction "GND_9") (pintype "passive"))
      (node (ref "U14") (pin "1") (pinfunction "GND_1") (pintype "passive"))
      (node (ref "U15") (pin "10") (pinfunction "RES_10") (pintype "passive"))
      (node (ref "U15") (pin "12") (pinfunction "GND_12") (pintype "passive"))
      (node (ref "U15") (pin "5") (pinfunction "GND_5") (pintype "passive"))
    )
    (net (code "46") (name "M3.3V") (class "Default")
      (node (ref "C194") (pin "1") (pinfunction "1_1") (pintype "passive"))
      (node (ref "C195") (pin "1") (pinfunction "1_1") (pintype "passive"))
      (node (ref "C196") (pin "1") (pinfunction "1_1") (pintype "passive"))
      (node (ref "C197") (pin "1") (pinfunction "1_1") (pintype "passive"))
      (node (ref "C199") (pin "1") (pinfunction "1_1") (pintype "passive"))
      (node (ref "Q23") (pin "3") (pinfunction "D_3") (pintype "passive"))
      (node (ref "R214") (pin "1") (pinfunction "1_1") (pintype "passive"))
      (node (ref "R215") (pin "2") (pinfunction "2_2") (pintype "passive"))
      (node (ref "R216") (pin "2") (pinfunction "2_2") (pintype "passive"))
      (node (ref "R220") (pin "1") (pinfunction "1_1") (pintype "passive"))
      (node (ref "R221") (pin "2") (pinfunction "2_2") (pintype "passive"))
      (node (ref "R229") (pin "1") (pinfunction "1_1") (pintype "passive"))
      (node (ref "R231") (pin "1") (pinfunction "1_1") (pintype "passive"))
      (node (ref "R233") (pin "1") (pinfunction "1_1") (pintype "passive"))
      (node (ref "R248") (pin "2") (pinfunction "2_2") (pintype "passive"))
      (node (ref "R250") (pin "2") (pinfunction "2_2") (pintype "passive"))
      (node (ref "U15") (pin "1") (pinfunction "VDD_IO_1") (pintype "passive"))
      (node (ref "U15") (pin "14") (pinfunction "VDD_14") (pintype "passive"))
    )
    (net (code "47") (name "Net-(C183-Pad1)") (class "Default")
      (node (ref "C183") (pin "1") (pinfunction "1_1") (pintype "passive"))
      (node (ref "C184") (pin "1") (pinfunction "1_1") (pintype "passive"))
      (node (ref "J11") (pin "3") (pinfunction "3_3") (pintype "passive"))
    )
    (net (code "48") (name "Net-(D28-K)") (class "Default")
      (node (ref "D28") (pin "2") (pinfunction "K_2") (pintype "passive"))
      (node (ref "U13") (pin "54") (pinfunction "VREG_ENABLE_54") (pintype "passive"))
    )
    (net (code "49") (name "Net-(D29-A)") (class "Default")
      (node (ref "C200") (pin "1") (pinfunction "1_1") (pintype "passive"))
      (node (ref "D29") (pin "1") (pinfunction "A_1") (pintype "passive"))
      (node (ref "Q24") (pin "1") (pinfunction "G_1") (pintype "passive"))
      (node (ref "R241") (pin "2") (pinfunction "2_2") (pintype "passive"))
    )
    (net (code "50") (name "Net-(LED2-A)") (class "Default")
      (node (ref "LED2") (pin "1") (pinfunction "A_1") (pintype "passive"))
      (node (ref "R229") (pin "2") (pinfunction "2_2") (pintype "passive"))
    )
    (net (code "51") (name "Net-(LED2-K)") (class "Default")
      (node (ref "C190") (pin "1") (pinfunction "1_1") (pintype "passive"))
      (node (ref "LED2") (pin "2") (pinfunction "K_2") (pintype "passive"))
      (node (ref "U13") (pin "27") (pinfunction "LED0_27") (pintype "passive"))
    )
    (net (code "52") (name "Net-(Q23-G)") (class "Default")
      (node (ref "Q23") (pin "1") (pinfunction "G_1") (pintype "passive"))
      (node (ref "R239") (pin "2") (pinfunction "2_2") (pintype "passive"))
      (node (ref "R240") (pin "1") (pinfunction "1_1") (pintype "passive"))
    )
    (net (code "53") (name "Net-(Q24-D)") (class "Default")
      (node (ref "Q24") (pin "3") (pinfunction "D_3") (pintype "passive"))
      (node (ref "R236") (pin "2") (pinfunction "2_2") (pintype "passive"))
    )
    (net (code "54") (name "Net-(Q25-B)") (class "Default")
      (node (ref "Q25") (pin "1") (pinfunction "B_1") (pintype "passive"))
      (node (ref "R249") (pin "2") (pinfunction "2_2") (pintype "passive"))
      (node (ref "R251") (pin "2") (pinfunction "2_2") (pintype "passive"))
    )
    (net (code "55") (name "Net-(Q25-C)") (class "Default")
      (node (ref "Q25") (pin "3") (pinfunction "C_3") (pintype "passive"))
      (node (ref "R240") (pin "2") (pinfunction "2_2") (pintype "passive"))
    )
    (net (code "56") (name "Net-(Q26-B)") (class "Default")
      (node (ref "Q26") (pin "1") (pinfunction "B_1") (pintype "passive"))
      (node (ref "R246") (pin "1") (pinfunction "1_1") (pintype "passive"))
      (node (ref "R252") (pin "2") (pinfunction "2_2") (pintype "passive"))
    )
    (net (code "57") (name "Net-(Q26-C)") (class "Default")
      (node (ref "Q26") (pin "3") (pinfunction "C_3") (pintype "passive"))
      (node (ref "R242") (pin "1") (pinfunction "1_1") (pintype "passive"))
      (node (ref "R243") (pin "2") (pinfunction "2_2") (pintype "passive"))
    )
    (net (code "58") (name "Net-(U13-CAP_SENSE_5)") (class "Default")
      (node (ref "R230") (pin "1") (pinfunction "1_1") (pintype "passive"))
      (node (ref "U13") (pin "15") (pinfunction "CAP_SENSE_5_15") (pintype "passive"))
    )
    (net (code "59") (name "Net-(U13-MIC_BIAS_A)") (class "Default")
      (node (ref "R227") (pin "2") (pinfunction "2_2") (pintype "passive"))
      (node (ref "U13") (pin "59") (pinfunction "MIC_BIAS_A_59") (pintype "passive"))
    )
    (net (code "60") (name "Net-(U13-MIC_BIAS_B)") (class "Default")
      (node (ref "R226") (pin "2") (pinfunction "2_2") (pintype "passive"))
      (node (ref "U13") (pin "62") (pinfunction "MIC_BIAS_B_62") (pintype "passive"))
    )
    (net (code "61") (name "Net-(U13-PIO2)") (class "Default")
      (node (ref "R219") (pin "2") (pinfunction "2_2") (pintype "passive"))
      (node (ref "U13") (pin "33") (pinfunction "PIO2_33") (pintype "passive"))
    )
    (net (code "62") (name "Net-(U13-PIO3)") (class "Default")
      (node (ref "C186") (pin "2") (pinfunction "2_2") (pintype "passive"))
      (node (ref "R218") (pin "2") (pinfunction "2_2") (pintype "passive"))
      (node (ref "U13") (pin "34") (pinfunction "PIO3_34") (pintype "passive"))
    )
    (net (code "63") (name "Net-(U13-PIO4)") (class "Default")
      (node (ref "R217") (pin "2") (pinfunction "2_2") (pintype "passive"))
      (node (ref "U13") (pin "35") (pinfunction "PIO4_35") (pintype "passive"))
    )
    (net (code "64") (name "Net-(U13-PIO12)") (class "Default")
      (node (ref "R225") (pin "1") (pinfunction "1_1") (pintype "passive"))
      (node (ref "U13") (pin "41") (pinfunction "PIO12_41") (pintype "passive"))
    )
    (net (code "65") (name "Net-(U13-PIO13)") (class "Default")
      (node (ref "R224") (pin "1") (pinfunction "1_1") (pintype "passive"))
      (node (ref "U13") (pin "42") (pinfunction "PIO13_42") (pintype "passive"))
    )
    (net (code "66") (name "Net-(U13-PIO14)") (class "Default")
      (node (ref "R223") (pin "1") (pinfunction "1_1") (pintype "passive"))
      (node (ref "U13") (pin "43") (pinfunction "PIO14_43") (pintype "passive"))
    )
    (net (code "67") (name "Net-(U13-PIO15)") (class "Default")
      (node (ref "R222") (pin "1") (pinfunction "1_1") (pintype "passive"))
      (node (ref "U13") (pin "44") (pinfunction "PIO15_44") (pintype "passive"))
    )
    (net (code "68") (name "Net-(U13-PIO_POWER)") (class "Default")
      (node (ref "R320") (pin "2") (pinfunction "2_2") (pintype "passive"))
      (node (ref "U13") (pin "48") (pinfunction "PIO_POWER_48") (pintype "passive"))
    )
    (net (code "69") (name "Net-(U13-RF_IO)") (class "Default")
      (node (ref "C183") (pin "2") (pinfunction "2_2") (pintype "passive"))
      (node (ref "C185") (pin "1") (pinfunction "1_1") (pintype "passive"))
      (node (ref "U13") (pin "8") (pinfunction "RF_IO_8") (pintype "passive"))
    )
    (net (code "70") (name "Net-(U13-UART_RTS)") (class "Default")
      (node (ref "R228") (pin "1") (pinfunction "1_1") (pintype "passive"))
      (node (ref "U13") (pin "56") (pinfunction "UART_RTS_56") (pintype "passive"))
    )
    (net (code "71") (name "Net-(U13-VBAT)") (class "Default")
      (node (ref "C191") (pin "1") (pinfunction "1_1") (pintype "passive"))
      (node (ref "C192") (pin "1") (pinfunction "1_1") (pintype "passive"))
      (node (ref "R319") (pin "2") (pinfunction "2_2") (pintype "passive"))
      (node (ref "R320") (pin "1") (pinfunction "1_1") (pintype "passive"))
      (node (ref "U13") (pin "50") (pinfunction "VBAT_50") (pintype "passive"))
      (node (ref "U13") (pin "51") (pinfunction "VBAT_SENSE_51") (pintype "passive"))
    )
    (net (code "72") (name "Net-(U14-~{RESET})") (class "Default")
      (node (ref "R237") (pin "1") (pinfunction "1_1") (pintype "passive"))
      (node (ref "U14") (pin "2") (pinfunction "~{RESET}_2") (pintype "passive"))
    )
    (net (code "73") (name "Net-(U15-ADC1)") (class "Default")
      (node (ref "R232") (pin "2") (pinfunction "2_2") (pintype "passive"))
      (node (ref "R233") (pin "2") (pinfunction "2_2") (pintype "passive"))
      (node (ref "U15") (pin "16") (pinfunction "ADC1_16") (pintype "passive"))
    )
    (net (code "74") (name "Net-(U15-ADC2)") (class "Default")
      (node (ref "R234") (pin "2") (pinfunction "2_2") (pintype "passive"))
      (node (ref "U15") (pin "15") (pinfunction "ADC2_15") (pintype "passive"))
    )
    (net (code "75") (name "Net-(U15-CS)") (class "Default")
      (node (ref "R250") (pin "1") (pinfunction "1_1") (pintype "passive"))
      (node (ref "U15") (pin "8") (pinfunction "CS_8") (pintype "passive"))
    )
    (net (code "76") (name "Net-(U15-SCL{slash}SPC)") (class "Default")
      (node (ref "R238") (pin "2") (pinfunction "2_2") (pintype "passive"))
      (node (ref "U15") (pin "4") (pinfunction "SCL/SPC_4") (pintype "passive"))
    )
    (net (code "77") (name "Net-(U15-SDA{slash}SDI{slash}SDO)") (class "Default")
      (node (ref "R247") (pin "2") (pinfunction "2_2") (pintype "passive"))
      (node (ref "U15") (pin "6") (pinfunction "SDA/SDI/SDO_6") (pintype "passive"))
    )
    (net (code "78") (name "Net-(U15-SDO{slash}SA0)") (class "Default")
      (node (ref "R248") (pin "1") (pinfunction "1_1") (pintype "passive"))
      (node (ref "U15") (pin "7") (pinfunction "SDO/SA0_7") (pintype "passive"))
    )
    (net (code "79") (name "unconnected-(U13-CAP_SENSE_0-Pad10)") (class "Default")
      (node (ref "U13") (pin "10") (pinfunction "CAP_SENSE_0_10") (pintype "passive+no_connect"))
    )
    (net (code "80") (name "unconnected-(U13-CAP_SENSE_1-Pad11)") (class "Default")
      (node (ref "U13") (pin "11") (pinfunction "CAP_SENSE_1_11") (pintype "passive+no_connect"))
    )
    (net (code "81") (name "unconnected-(U13-CAP_SENSE_2-Pad12)") (class "Default")
      (node (ref "U13") (pin "12") (pinfunction "CAP_SENSE_2_12") (pintype "passive+no_connect"))
    )
    (net (code "82") (name "unconnected-(U13-CAP_SENSE_3-Pad13)") (class "Default")
      (node (ref "U13") (pin "13") (pinfunction "CAP_SENSE_3_13") (pintype "passive+no_connect"))
    )
    (net (code "83") (name "unconnected-(U13-CHG_EXT-Pad53)") (class "Default")
      (node (ref "U13") (pin "53") (pinfunction "CHG_EXT_53") (pintype "passive+no_connect"))
    )
    (net (code "84") (name "unconnected-(U13-MIC_LN-Pad57)") (class "Default")
      (node (ref "U13") (pin "57") (pinfunction "MIC_LN_57") (pintype "passive+no_connect"))
    )
    (net (code "85") (name "unconnected-(U13-MIC_LP-Pad58)") (class "Default")
      (node (ref "U13") (pin "58") (pinfunction "MIC_LP_58") (pintype "passive+no_connect"))
    )
    (net (code "86") (name "unconnected-(U13-MIC_RN-Pad60)") (class "Default")
      (node (ref "U13") (pin "60") (pinfunction "MIC_RN_60") (pintype "passive+no_connect"))
    )
    (net (code "87") (name "unconnected-(U13-MIC_RP-Pad61)") (class "Default")
      (node (ref "U13") (pin "61") (pinfunction "MIC_RP_61") (pintype "passive+no_connect"))
    )
    (net (code "88") (name "unconnected-(U13-SPKR_LN-Pad3)") (class "Default")
      (node (ref "U13") (pin "3") (pinfunction "SPKR_LN_3") (pintype "passive+no_connect"))
    )
    (net (code "89") (name "unconnected-(U13-SPKR_LP-Pad4)") (class "Default")
      (node (ref "U13") (pin "4") (pinfunction "SPKR_LP_4") (pintype "passive+no_connect"))
    )
    (net (code "90") (name "unconnected-(U13-SPKR_RN-Pad1)") (class "Default")
      (node (ref "U13") (pin "1") (pinfunction "SPKR_RN_1") (pintype "passive+no_connect"))
    )
    (net (code "91") (name "unconnected-(U13-SPKR_RP-Pad2)") (class "Default")
      (node (ref "U13") (pin "2") (pinfunction "SPKR_RP_2") (pintype "passive+no_connect"))
    )
    (net (code "92") (name "unconnected-(U13-UART_CTS-Pad55)") (class "Default")
      (node (ref "U13") (pin "55") (pinfunction "UART_CTS_55") (pintype "passive+no_connect"))
    )
    (net (code "93") (name "unconnected-(U13-UART_RX-Pad25)") (class "Default")
      (node (ref "U13") (pin "25") (pinfunction "UART_RX_25") (pintype "passive+no_connect"))
    )
    (net (code "94") (name "unconnected-(U13-UART_TX-Pad26)") (class "Default")
      (node (ref "U13") (pin "26") (pinfunction "UART_TX_26") (pintype "passive+no_connect"))
    )
    (net (code "95") (name "unconnected-(U15-ADC3-Pad13)") (class "Default")
      (node (ref "U15") (pin "13") (pinfunction "ADC3_13") (pintype "passive"))
    )
    (net (code "96") (name "unconnected-(U15-INT1-Pad11)") (class "Default")
      (node (ref "U15") (pin "11") (pinfunction "INT1_11") (pintype "passive"))
    )
    (net (code "97") (name "unconnected-(U15-INT2-Pad9)") (class "Default")
      (node (ref "U15") (pin "9") (pinfunction "INT2_9") (pintype "passive"))
    )
    (net (code "98") (name "unconnected-(U15-NC-Pad2)") (class "Default")
      (node (ref "U15") (pin "2") (pinfunction "NC_2") (pintype "passive+no_connect"))
    )
    (net (code "99") (name "unconnected-(U15-NC-Pad3)") (class "Default")
      (node (ref "U15") (pin "3") (pinfunction "NC_3") (pintype "passive+no_connect"))
    )
  )
)
